# CurrentSource.net
KiCad netlist of a schematic drawn in Altium Designer
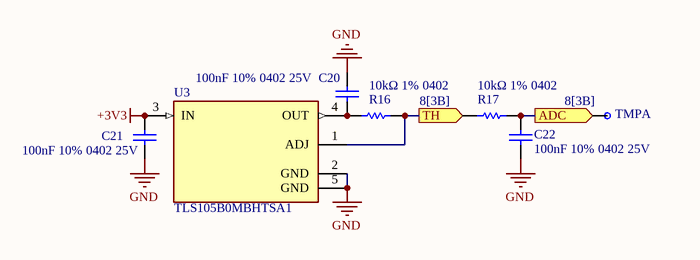
[diagram p0: CurrentSource.SchDoc]

(export (version "E")
  (design (tool "Eeschema 10.0.6"))
  (components
    (comp (ref "C20")
      (value "100nF 10% 0402 25V")
      (footprint "0402N")
      (fields (field (name "TOLERANCE") "10") (field (name "VOLTAGE") "25"))
      (libsource (lib "MiscPassives") (part "C0402"))
    )
    (comp (ref "C21")
      (value "100nF 10% 0402 25V")
      (footprint "0402N")
      (fields (field (name "TOLERANCE") "10") (field (name "VOLTAGE") "25"))
      (libsource (lib "MiscPassives") (part "C0402"))
    )
    (comp (ref "C22")
      (value "100nF 10% 0402 25V")
      (footprint "0402N")
      (fields (field (name "TOLERANCE") "10") (field (name "VOLTAGE") "25"))
      (libsource (lib "MiscPassives") (part "C0402"))
    )
    (comp (ref "R16")
      (value "10kΩ 1% 0402")
      (footprint "0402N")
      (fields (field (name "TOLERANCE") "1"))
      (libsource (lib "MiscPassives") (part "R0402"))
    )
    (comp (ref "R17")
      (value "10kΩ 1% 0402")
      (footprint "0402N")
      (fields (field (name "TOLERANCE") "1"))
      (libsource (lib "MiscPassives") (part "R0402"))
    )
    (comp (ref "TMPA")
      (value "Testpoint")
      (footprint "Testpoint-Footprint-1")
      (libsource (lib "Saule S.A") (part "Testpoint"))
    )
    (comp (ref "U3")
      (value "TLS105B0MBHTSA1")
      (footprint "FP-PG-SCT595-5-MFG")
      (description "IC REG LIN POS ADJ 120MA SCT595")
      (libsource (lib "Altium Content Vault") (part "186989d30c5f6c9514ab6b5bd9bd7ce"))
    )
  )
  (nets
    (net (code "1") (name "+3V3") (class "Default")
      (node (ref "C21") (pin "2") (pinfunction "2_2") (pintype "passive"))
      (node (ref "U3") (pin "3") (pinfunction "IN_3") (pintype "input"))
    )
    (net (code "2") (name "/ADC") (class "Default")
      (node (ref "C22") (pin "2") (pinfunction "2_2") (pintype "passive"))
      (node (ref "R17") (pin "2") (pinfunction "2_2") (pintype "passive"))
      (node (ref "TMPA") (pin "1") (pinfunction "1_1") (pintype "passive"))
    )
    (net (code "3") (name "/TH") (class "Default")
      (node (ref "R16") (pin "2") (pinfunction "2_2") (pintype "passive"))
      (node (ref "R17") (pin "1") (pinfunction "1_1") (pintype "passive"))
      (node (ref "U3") (pin "1") (pinfunction "ADJ_1") (pintype "passive"))
    )
    (net (code "4") (name "GND") (class "Default")
      (node (ref "C20") (pin "1") (pinfunction "1_1") (pintype "passive"))
      (node (ref "C21") (pin "1") (pinfunction "1_1") (pintype "passive"))
      (node (ref "C22") (pin "1") (pinfunction "1_1") (pintype "passive"))
      (node (ref "U3") (pin "2") (pinfunction "GND_2") (pintype "power_in"))
      (node (ref "U3") (pin "5") (pinfunction "GND_5") (pintype "power_in"))
    )
    (net (code "5") (name "Net-(U3-OUT)") (class "Default")
      (node (ref "C20") (pin "2") (pinfunction "2_2") (pintype "passive"))
      (node (ref "R16") (pin "1") (pinfunction "1_1") (pintype "passive"))
      (node (ref "U3") (pin "4") (pinfunction "OUT_4") (pintype "output"))
    )
  )
)
